# ADC_MAX1037.net
KiCad netlist of a schematic drawn in Altium Designer
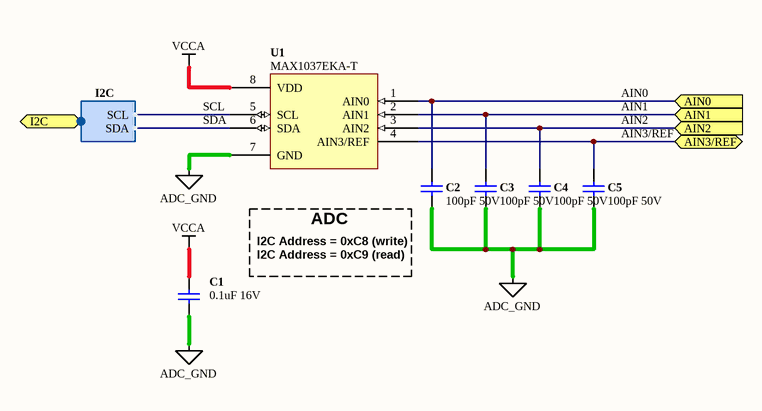
[diagram p0: ADC_MAX1037.SchDoc]

(export (version "E")
  (design (tool "Eeschema 10.0.6"))
  (components
    (comp (ref "C1")
      (value "0.1uF 16V")
      (footprint "CAPC1005-STAR")
      (description "Capacitor, Ceramic, 0.1uF 10% 16V 0402 (1005) X7R")
      (fields (field (name "TOLERANCE") "10 %"))
      (libsource (lib "altium-import") (part "root_0_CAP-NP_"))
    )
    (comp (ref "C2")
      (value "100pF 50V")
      (footprint "CAPC1005-STAR")
      (description "Capacitor, Ceramic, 100pF 5% 50V 0402 (1005) COG")
      (fields (field (name "TOLERANCE") "5 %"))
      (libsource (lib "altium-import") (part "root_0_CAP-NP_"))
    )
    (comp (ref "C3")
      (value "100pF 50V")
      (footprint "CAPC1005-STAR")
      (description "Capacitor, Ceramic, 100pF 5% 50V 0402 (1005) COG")
      (fields (field (name "TOLERANCE") "5 %"))
      (libsource (lib "altium-import") (part "root_0_CAP-NP_"))
    )
    (comp (ref "C4")
      (value "100pF 50V")
      (footprint "CAPC1005-STAR")
      (description "Capacitor, Ceramic, 100pF 5% 50V 0402 (1005) COG")
      (fields (field (name "TOLERANCE") "5 %"))
      (libsource (lib "altium-import") (part "root_0_CAP-NP_"))
    )
    (comp (ref "C5")
      (value "100pF 50V")
      (footprint "CAPC1005-STAR")
      (description "Capacitor, Ceramic, 100pF 5% 50V 0402 (1005) COG")
      (fields (field (name "TOLERANCE") "5 %"))
      (libsource (lib "altium-import") (part "root_0_CAP-NP_"))
    )
    (comp (ref "U1")
      (value "MAX1037EKA-T")
      (footprint "SOT65P280-8")
      (description "MAX1037EKA-T, 2.7V to 5.5V, Low-Power, 4-Channel, I2C, 8-Bit ADCs")
      (libsource (lib "altium-import") (part "root_0_mirrored_MAX1037_"))
    )
  )
  (nets
    (net (code "2") (name "/AIN0") (class "Default")
      (node (ref "C2") (pin "1") (pinfunction "1_1") (pintype "passive"))
      (node (ref "U1") (pin "1") (pinfunction "AIN0_1") (pintype "input"))
    )
    (net (code "3") (name "/AIN1") (class "Default")
      (node (ref "C3") (pin "1") (pinfunction "1_1") (pintype "passive"))
      (node (ref "U1") (pin "2") (pinfunction "AIN1_2") (pintype "input"))
    )
    (net (code "4") (name "/AIN2") (class "Default")
      (node (ref "C4") (pin "1") (pinfunction "1_1") (pintype "passive"))
      (node (ref "U1") (pin "3") (pinfunction "AIN2_3") (pintype "input"))
    )
    (net (code "5") (name "/AIN3{slash}REF") (class "Default")
      (node (ref "C5") (pin "1") (pinfunction "1_1") (pintype "passive"))
      (node (ref "U1") (pin "4") (pinfunction "AIN3/REF_4") (pintype "power_in"))
    )
    (net (code "6") (name "/SCL") (class "Default")
      (node (ref "U1") (pin "5") (pinfunction "SCL_5") (pintype "bidirectional"))
    )
    (net (code "7") (name "/SDA") (class "Default")
      (node (ref "U1") (pin "6") (pinfunction "SDA_6") (pintype "bidirectional"))
    )
    (net (code "9") (name "ADC_GND") (class "Default")
      (node (ref "C1") (pin "2") (pinfunction "2_2") (pintype "passive"))
      (node (ref "C2") (pin "2") (pinfunction "2_2") (pintype "passive"))
      (node (ref "C3") (pin "2") (pinfunction "2_2") (pintype "passive"))
      (node (ref "C4") (pin "2") (pinfunction "2_2") (pintype "passive"))
      (node (ref "C5") (pin "2") (pinfunction "2_2") (pintype "passive"))
      (node (ref "U1") (pin "7") (pinfunction "GND_7") (pintype "power_in"))
    )
    (net (code "10") (name "VCCA") (class "Default")
      (node (ref "C1") (pin "1") (pinfunction "1_1") (pintype "passive"))
      (node (ref "U1") (pin "8") (pinfunction "VDD_8") (pintype "power_in"))
    )
  )
)
